# MyDoorSensor.net
KiCad netlist of a schematic drawn in EAGLE
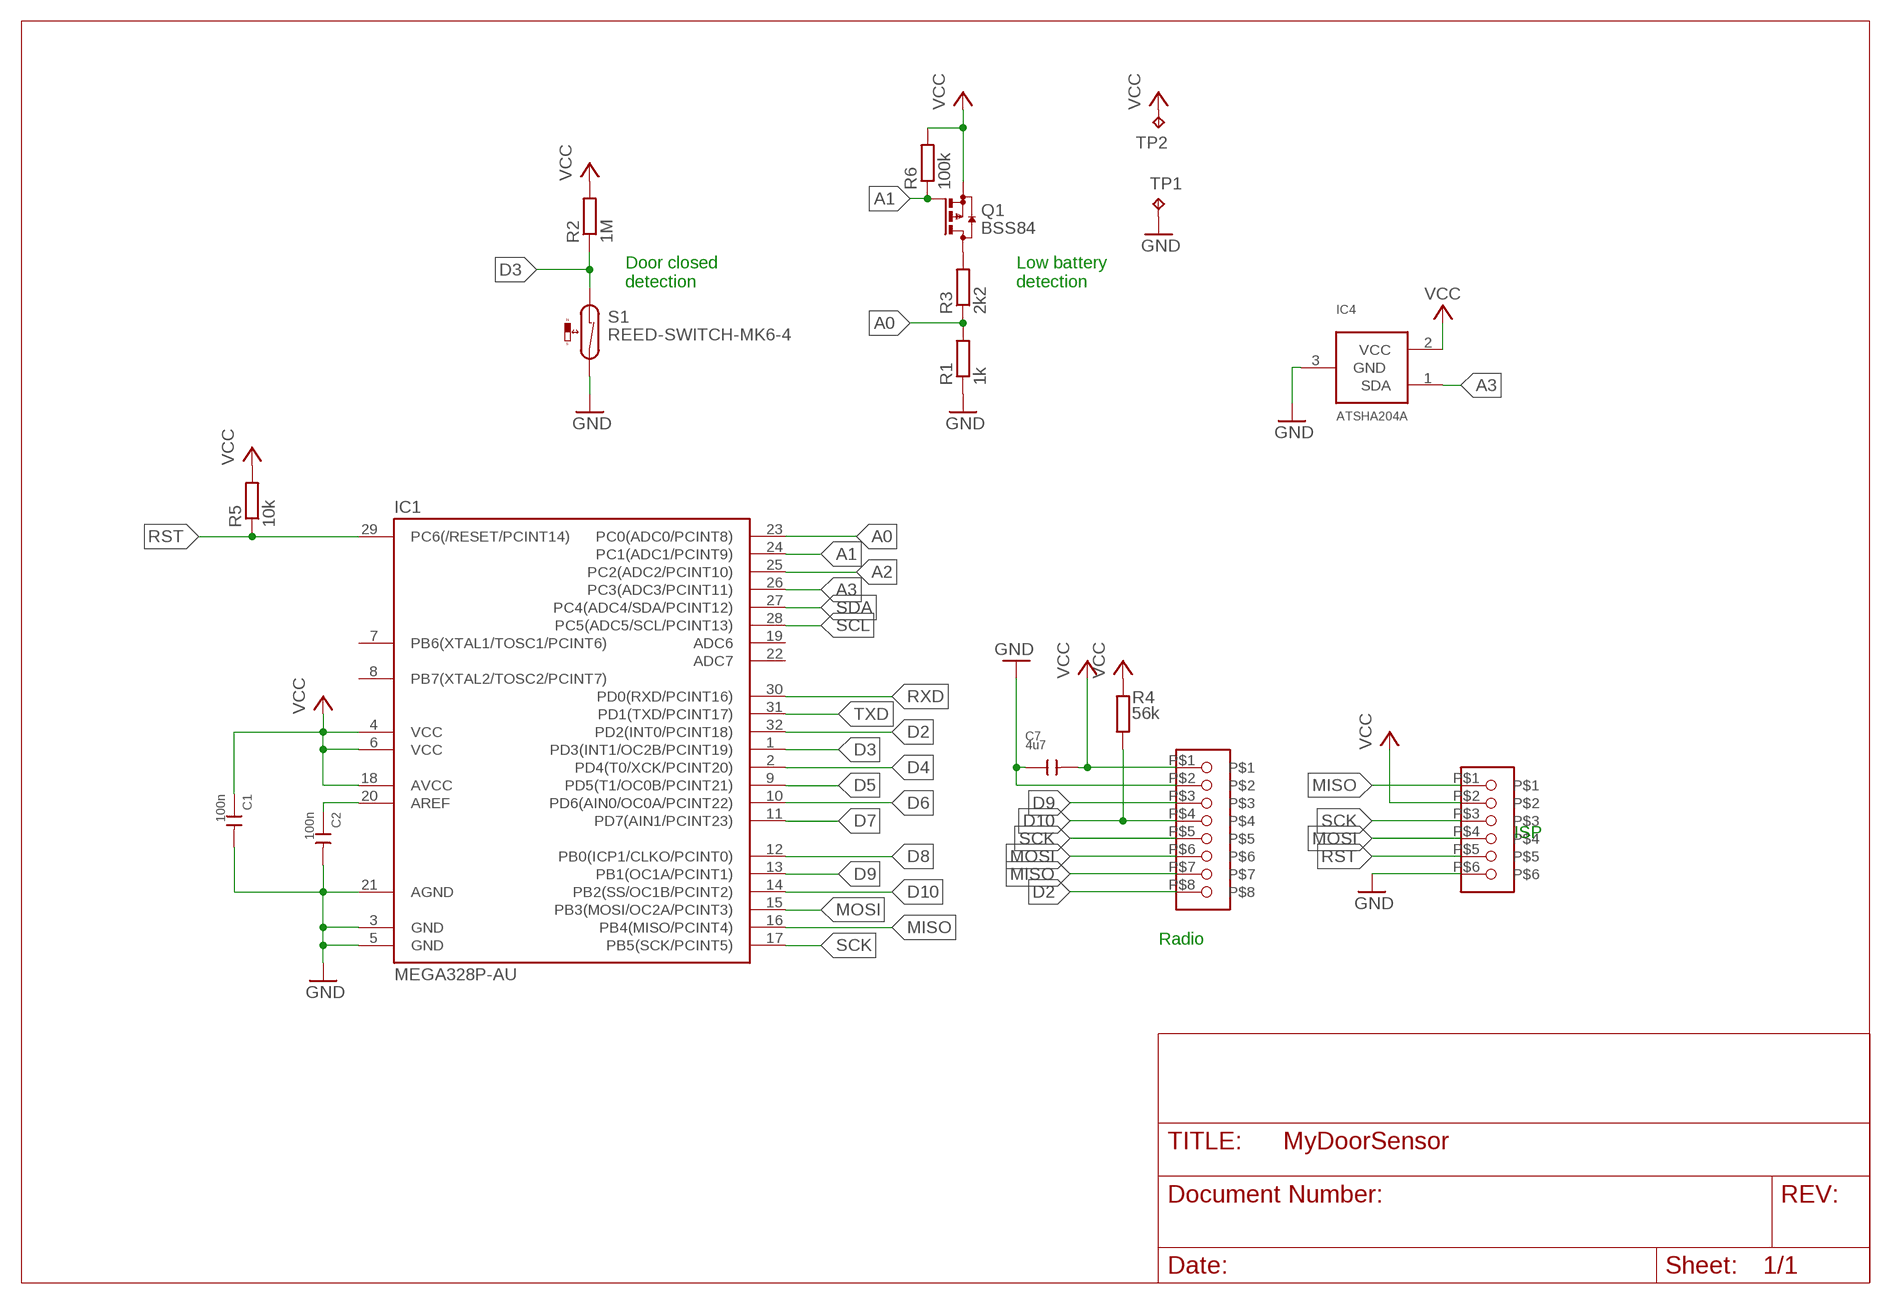
[diagram p0: schematic, sheet 1]

(export (version "E")
  (design (tool "Eeschema 10.0.6"))
  (components
    (comp (ref "C1")
      (value "100n")
      (footprint "eagle-import:C0603")
      (libsource (lib "eagle-import") (part "CAP-0603"))
    )
    (comp (ref "C2")
      (value "100n")
      (footprint "eagle-import:C0603")
      (libsource (lib "eagle-import") (part "CAP-0603"))
    )
    (comp (ref "C7")
      (value "4u7")
      (footprint "eagle-import:C0805")
      (libsource (lib "eagle-import") (part "CAP-0805"))
    )
    (comp (ref "IC1")
      (value "MEGA328P-AU")
      (footprint "eagle-import:TQFP32-08")
      (libsource (lib "eagle-import") (part "MEGA48/88/168-AU"))
    )
    (comp (ref "IC4")
      (value "ATSHA204A")
      (footprint "eagle-import:SOT23")
      (libsource (lib "eagle-import") (part "ATSHA204A"))
    )
    (comp (ref "Q1")
      (value "BSS84")
      (footprint "eagle-import:SOT23")
      (libsource (lib "eagle-import") (part "BSS84"))
    )
    (comp (ref "R1")
      (value "1k")
      (footprint "eagle-import:R0805")
      (libsource (lib "eagle-import") (part "R-EU_R0805"))
    )
    (comp (ref "R2")
      (value "1M")
      (footprint "eagle-import:R0805")
      (libsource (lib "eagle-import") (part "R-EU_R0805"))
    )
    (comp (ref "R3")
      (value "2k2")
      (footprint "eagle-import:R0805")
      (libsource (lib "eagle-import") (part "R-EU_R0805"))
    )
    (comp (ref "R4")
      (value "56k")
      (footprint "eagle-import:R0805")
      (libsource (lib "eagle-import") (part "R-EU_R0805"))
    )
    (comp (ref "R5")
      (value "10k")
      (footprint "eagle-import:R0805")
      (libsource (lib "eagle-import") (part "R-EU_R0805"))
    )
    (comp (ref "R6")
      (value "100k")
      (footprint "eagle-import:R0805")
      (libsource (lib "eagle-import") (part "R-EU_R0805"))
    )
    (comp (ref "S1")
      (value "REED-SWITCH-MK6-4")
      (footprint "eagle-import:MK6-4")
      (libsource (lib "eagle-import") (part "REED-SWITCH-MK6-4"))
    )
    (comp (ref "TP1")
      (value "TPPAD1-13")
      (footprint "eagle-import:P1-13")
      (libsource (lib "eagle-import") (part "TPPAD1-13"))
    )
    (comp (ref "TP2")
      (value "TPPAD1-13")
      (footprint "eagle-import:P1-13")
      (libsource (lib "eagle-import") (part "TPPAD1-13"))
    )
    (comp (ref "U$1")
      (value "NRF24")
      (footprint "eagle-import:PINHD-1X08_NRF24")
      (libsource (lib "eagle-import") (part "NRF24"))
    )
    (comp (ref "U$2")
      (value "ISP")
      (footprint "eagle-import:ISP")
      (libsource (lib "eagle-import") (part "ISP"))
    )
  )
  (nets
    (net (code "1") (name "A0") (class "Default")
      (node (ref "IC1") (pin "23") (pinfunction "PC0(ADC0/PCINT8)_23") (pintype "bidirectional"))
      (node (ref "R1") (pin "2") (pinfunction "2_2") (pintype "passive"))
      (node (ref "R3") (pin "1") (pinfunction "1_1") (pintype "passive"))
    )
    (net (code "2") (name "A1") (class "Default")
      (node (ref "IC1") (pin "24") (pinfunction "PC1(ADC1/PCINT9)_24") (pintype "bidirectional"))
      (node (ref "Q1") (pin "1") (pinfunction "G_1") (pintype "passive"))
      (node (ref "R6") (pin "1") (pinfunction "1_1") (pintype "passive"))
    )
    (net (code "3") (name "A2") (class "Default")
      (node (ref "IC1") (pin "25") (pinfunction "PC2(ADC2/PCINT10)_25") (pintype "bidirectional"))
    )
    (net (code "4") (name "A3") (class "Default")
      (node (ref "IC1") (pin "26") (pinfunction "PC3(ADC3/PCINT11)_26") (pintype "bidirectional"))
      (node (ref "IC4") (pin "1") (pinfunction "SDA_1") (pintype "bidirectional"))
    )
    (net (code "5") (name "D2") (class "Default")
      (node (ref "IC1") (pin "32") (pinfunction "PD2(INT0/PCINT18)_32") (pintype "bidirectional"))
      (node (ref "U$1") (pin "P$8") (pinfunction "P$8_P$8") (pintype "bidirectional"))
    )
    (net (code "6") (name "D3") (class "Default")
      (node (ref "IC1") (pin "1") (pinfunction "PD3(INT1/OC2B/PCINT19)_1") (pintype "bidirectional"))
      (node (ref "R2") (pin "1") (pinfunction "1_1") (pintype "passive"))
      (node (ref "S1") (pin "1") (pinfunction "1_1") (pintype "passive"))
    )
    (net (code "7") (name "D4") (class "Default")
      (node (ref "IC1") (pin "2") (pinfunction "PD4(T0/XCK/PCINT20)_2") (pintype "bidirectional"))
    )
    (net (code "8") (name "D5") (class "Default")
      (node (ref "IC1") (pin "9") (pinfunction "PD5(T1/OC0B/PCINT21)_9") (pintype "bidirectional"))
    )
    (net (code "9") (name "D6") (class "Default")
      (node (ref "IC1") (pin "10") (pinfunction "PD6(AIN0/OC0A/PCINT22)_10") (pintype "bidirectional"))
    )
    (net (code "10") (name "D7") (class "Default")
      (node (ref "IC1") (pin "11") (pinfunction "PD7(AIN1/PCINT23)_11") (pintype "bidirectional"))
    )
    (net (code "11") (name "D8") (class "Default")
      (node (ref "IC1") (pin "12") (pinfunction "PB0(ICP1/CLKO/PCINT0)_12") (pintype "bidirectional"))
    )
    (net (code "12") (name "D9") (class "Default")
      (node (ref "IC1") (pin "13") (pinfunction "PB1(OC1A/PCINT1)_13") (pintype "bidirectional"))
      (node (ref "U$1") (pin "P$3") (pinfunction "P$3_P$3") (pintype "bidirectional"))
    )
    (net (code "13") (name "D10") (class "Default")
      (node (ref "IC1") (pin "14") (pinfunction "PB2(SS/OC1B/PCINT2)_14") (pintype "bidirectional"))
      (node (ref "R4") (pin "1") (pinfunction "1_1") (pintype "passive"))
      (node (ref "U$1") (pin "P$4") (pinfunction "P$4_P$4") (pintype "bidirectional"))
    )
    (net (code "14") (name "GND") (class "Default")
      (node (ref "C1") (pin "2") (pinfunction "2_2") (pintype "passive"))
      (node (ref "C2") (pin "2") (pinfunction "2_2") (pintype "passive"))
      (node (ref "C7") (pin "1") (pinfunction "1_1") (pintype "passive"))
      (node (ref "IC1") (pin "21") (pinfunction "AGND_21") (pintype "power_in"))
      (node (ref "IC1") (pin "3") (pinfunction "GND_3") (pintype "power_in"))
      (node (ref "IC1") (pin "5") (pinfunction "GND_5") (pintype "power_in"))
      (node (ref "IC4") (pin "3") (pinfunction "GND_3") (pintype "bidirectional"))
      (node (ref "R1") (pin "1") (pinfunction "1_1") (pintype "passive"))
      (node (ref "S1") (pin "2") (pinfunction "2_2") (pintype "passive"))
      (node (ref "TP1") (pin "TP") (pinfunction "TP_TP") (pintype "input"))
      (node (ref "U$1") (pin "P$2") (pinfunction "P$2_P$2") (pintype "bidirectional"))
      (node (ref "U$2") (pin "P$6") (pinfunction "P$6_P$6") (pintype "bidirectional"))
    )
    (net (code "15") (name "MISO") (class "Default")
      (node (ref "IC1") (pin "16") (pinfunction "PB4(MISO/PCINT4)_16") (pintype "bidirectional"))
      (node (ref "U$1") (pin "P$7") (pinfunction "P$7_P$7") (pintype "bidirectional"))
      (node (ref "U$2") (pin "P$1") (pinfunction "P$1_P$1") (pintype "bidirectional"))
    )
    (net (code "16") (name "MOSI") (class "Default")
      (node (ref "IC1") (pin "15") (pinfunction "PB3(MOSI/OC2A/PCINT3)_15") (pintype "bidirectional"))
      (node (ref "U$1") (pin "P$6") (pinfunction "P$6_P$6") (pintype "bidirectional"))
      (node (ref "U$2") (pin "P$4") (pinfunction "P$4_P$4") (pintype "bidirectional"))
    )
    (net (code "17") (name "Net-(IC1-AREF)") (class "Default")
      (node (ref "C2") (pin "1") (pinfunction "1_1") (pintype "passive"))
      (node (ref "IC1") (pin "20") (pinfunction "AREF_20") (pintype "passive"))
    )
    (net (code "18") (name "Net-(Q1-D)") (class "Default")
      (node (ref "Q1") (pin "3") (pinfunction "D_3") (pintype "passive"))
      (node (ref "R3") (pin "2") (pinfunction "2_2") (pintype "passive"))
    )
    (net (code "19") (name "RST") (class "Default")
      (node (ref "IC1") (pin "29") (pinfunction "PC6(/RESET/PCINT14)_29") (pintype "bidirectional"))
      (node (ref "R5") (pin "1") (pinfunction "1_1") (pintype "passive"))
      (node (ref "U$2") (pin "P$5") (pinfunction "P$5_P$5") (pintype "bidirectional"))
    )
    (net (code "20") (name "RXD") (class "Default")
      (node (ref "IC1") (pin "30") (pinfunction "PD0(RXD/PCINT16)_30") (pintype "bidirectional"))
    )
    (net (code "21") (name "SCK") (class "Default")
      (node (ref "IC1") (pin "17") (pinfunction "PB5(SCK/PCINT5)_17") (pintype "bidirectional"))
      (node (ref "U$1") (pin "P$5") (pinfunction "P$5_P$5") (pintype "bidirectional"))
      (node (ref "U$2") (pin "P$3") (pinfunction "P$3_P$3") (pintype "bidirectional"))
    )
    (net (code "22") (name "SCL") (class "Default")
      (node (ref "IC1") (pin "28") (pinfunction "PC5(ADC5/SCL/PCINT13)_28") (pintype "bidirectional"))
    )
    (net (code "23") (name "SDA") (class "Default")
      (node (ref "IC1") (pin "27") (pinfunction "PC4(ADC4/SDA/PCINT12)_27") (pintype "bidirectional"))
    )
    (net (code "24") (name "TXD") (class "Default")
      (node (ref "IC1") (pin "31") (pinfunction "PD1(TXD/PCINT17)_31") (pintype "bidirectional"))
    )
    (net (code "25") (name "VCC") (class "Default")
      (node (ref "C1") (pin "1") (pinfunction "1_1") (pintype "passive"))
      (node (ref "C7") (pin "2") (pinfunction "2_2") (pintype "passive"))
      (node (ref "IC1") (pin "18") (pinfunction "AVCC_18") (pintype "passive"))
      (node (ref "IC1") (pin "4") (pinfunction "VCC_4") (pintype "power_in"))
      (node (ref "IC1") (pin "6") (pinfunction "VCC_6") (pintype "power_in"))
      (node (ref "IC4") (pin "2") (pinfunction "VCC_2") (pintype "bidirectional"))
      (node (ref "Q1") (pin "2") (pinfunction "S_2") (pintype "passive"))
      (node (ref "R2") (pin "2") (pinfunction "2_2") (pintype "passive"))
      (node (ref "R4") (pin "2") (pinfunction "2_2") (pintype "passive"))
      (node (ref "R5") (pin "2") (pinfunction "2_2") (pintype "passive"))
      (node (ref "R6") (pin "2") (pinfunction "2_2") (pintype "passive"))
      (node (ref "TP2") (pin "TP") (pinfunction "TP_TP") (pintype "input"))
      (node (ref "U$1") (pin "P$1") (pinfunction "P$1_P$1") (pintype "bidirectional"))
      (node (ref "U$2") (pin "P$2") (pinfunction "P$2_P$2") (pintype "bidirectional"))
    )
    (net (code "26") (name "unconnected-(IC1-ADC6-Pad19)") (class "Default")
      (node (ref "IC1") (pin "19") (pinfunction "ADC6_19") (pintype "passive"))
    )
    (net (code "27") (name "unconnected-(IC1-ADC7-Pad22)") (class "Default")
      (node (ref "IC1") (pin "22") (pinfunction "ADC7_22") (pintype "passive"))
    )
    (net (code "28") (name "unconnected-(IC1-PB6(XTAL1{slash}TOSC1{slash}PCINT6)-Pad7)") (class "Default")
      (node (ref "IC1") (pin "7") (pinfunction "PB6(XTAL1/TOSC1/PCINT6)_7") (pintype "bidirectional"))
    )
    (net (code "29") (name "unconnected-(IC1-PB7(XTAL2{slash}TOSC2{slash}PCINT7)-Pad8)") (class "Default")
      (node (ref "IC1") (pin "8") (pinfunction "PB7(XTAL2/TOSC2/PCINT7)_8") (pintype "bidirectional"))
    )
  )
)
